# motordriver-v4_0_stspin.net
KiCad netlist of a schematic drawn in Altium Designer
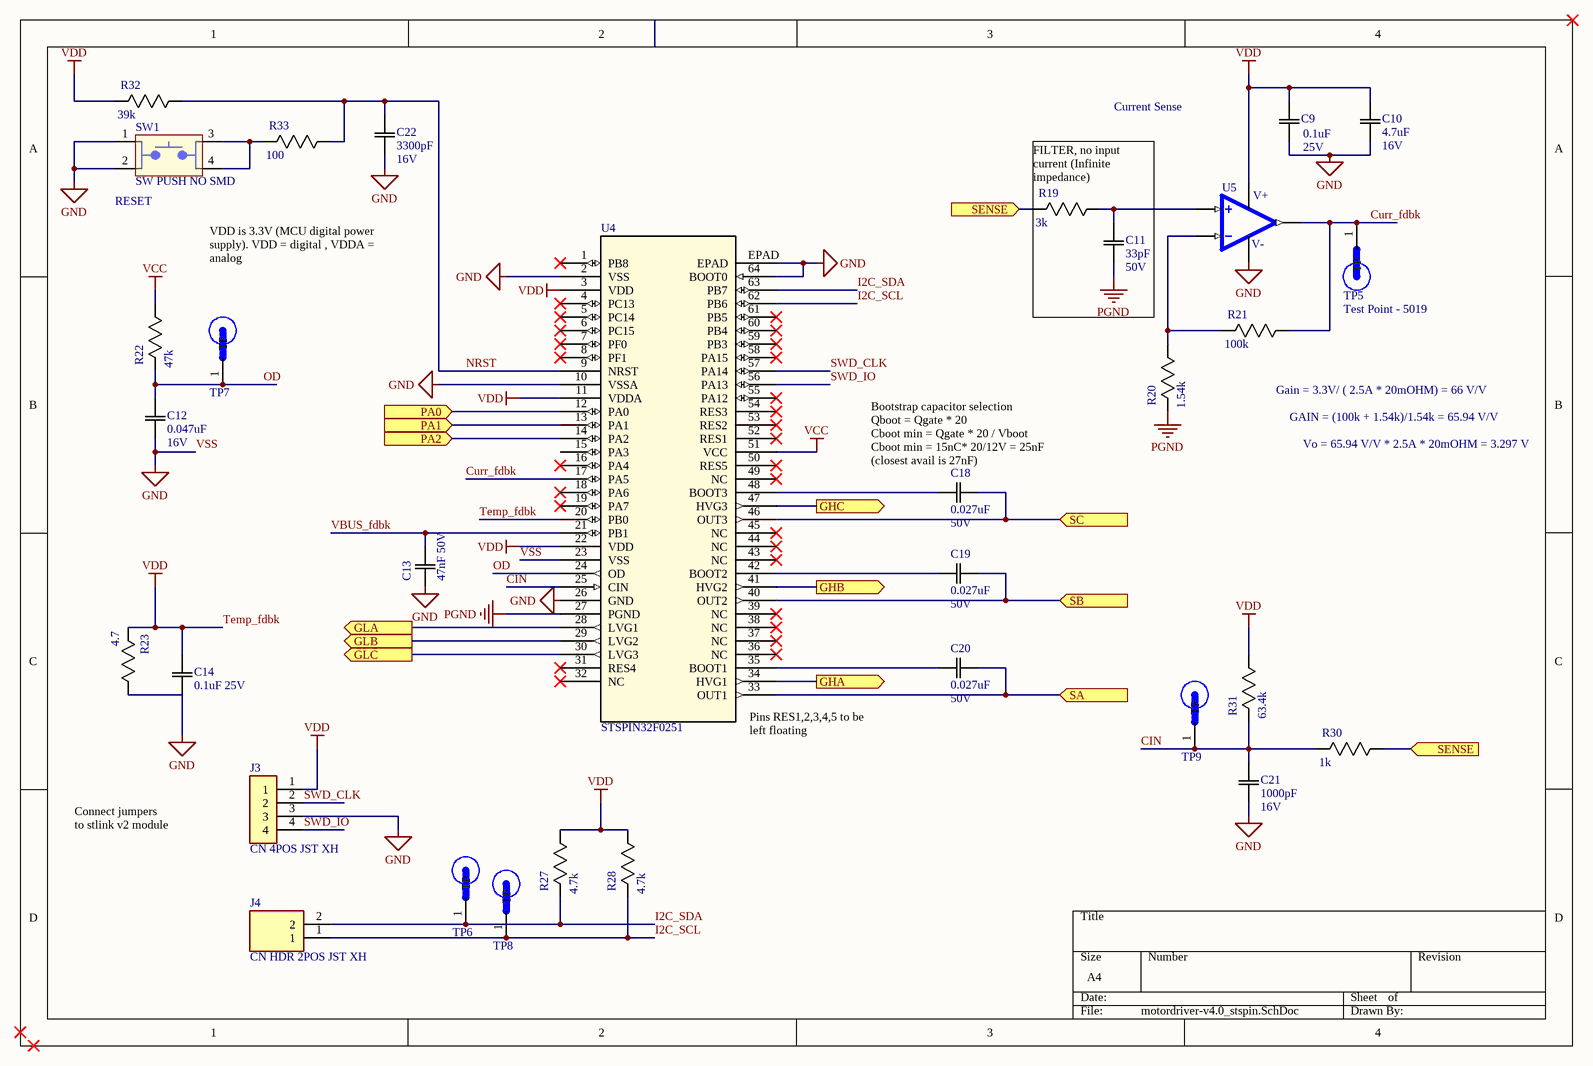
[diagram p0: motordriver-v4.0_stspin.SchDoc]

(export (version "E")
  (design (tool "Eeschema 10.0.6"))
  (components
    (comp (ref "C9")
      (value "0.1uF")
      (footprint "0805")
      (description "CAP CER 0.1UF 25V X7R 0805")
      (fields
        (field (name "TOLERANCE") "10%")
        (field (name "RATING") "25V")
        (field (name "Comment") "0.1uF 25V")
      )
      (libsource (lib "AltiumLibraries") (part "CAP 0.1uF 25V"))
    )
    (comp (ref "C10")
      (value "4.7uF")
      (footprint "0603")
      (description "CAP CER 4.7UF 16V X5R 0603/0805")
      (fields (field (name "TOLERANCE") "10%") (field (name "RATING") "16V"))
      (libsource (lib "AltiumLibraries") (part "CAP 4.7uF 16V"))
    )
    (comp (ref "C11")
      (value "33pF")
      (footprint "0603")
      (description "CAP CER 33PF 50V X7R 0603/0805")
      (fields (field (name "TOLERANCE") "10%") (field (name "RATING") "50V"))
      (libsource (lib "AltiumLibraries") (part "CAP 33pF 50V"))
    )
    (comp (ref "C12")
      (value "0.047uF")
      (footprint "0603")
      (description "CAP CER 0.047UF 16V X5R 0603/0805")
      (fields (field (name "TOLERANCE") "10%") (field (name "RATING") "16V"))
      (libsource (lib "AltiumLibraries") (part "CAP 0.047uF 16V"))
    )
    (comp (ref "C13")
      (value "47nF 50V")
      (footprint "0805")
      (description "CAP CER 0.047UF 50V X7R 0805")
      (fields (field (name "TOLERANCE") "5%"))
      (libsource (lib "AltiumLibraries") (part "CAP 47nF 50V"))
    )
    (comp (ref "C14")
      (value "0.1uF 25V")
      (footprint "0805")
      (description "CAP CER 0.1UF 25V X7R 0805")
      (fields (field (name "TOLERANCE") "10%"))
      (libsource (lib "AltiumLibraries") (part "CAP 0.1uF 25V"))
    )
    (comp (ref "C18")
      (value "0.027uF")
      (footprint "0805")
      (description "CAP CER 0.027UF 50V X7R 0805")
      (fields (field (name "TOLERANCE") "5%") (field (name "RATING") "50V"))
      (libsource (lib "AltiumLibraries") (part "CAP 0.027UF 50V X7R 0805"))
    )
    (comp (ref "C19")
      (value "0.027uF")
      (footprint "0805")
      (description "CAP CER 0.027UF 50V X7R 0805")
      (fields (field (name "TOLERANCE") "5%") (field (name "RATING") "50V"))
      (libsource (lib "AltiumLibraries") (part "CAP 0.027UF 50V X7R 0805"))
    )
    (comp (ref "C20")
      (value "0.027uF")
      (footprint "0805")
      (description "CAP CER 0.027UF 50V X7R 0805")
      (fields (field (name "TOLERANCE") "5%") (field (name "RATING") "50V"))
      (libsource (lib "AltiumLibraries") (part "CAP 0.027UF 50V X7R 0805"))
    )
    (comp (ref "C21")
      (value "1000pF")
      (footprint "0603")
      (description "CAP CER 1000PF 16V X5R 0603/0805")
      (fields (field (name "TOLERANCE") "10%") (field (name "RATING") "16V"))
      (libsource (lib "AltiumLibraries") (part "CAP 1000pF 16V"))
    )
    (comp (ref "C22")
      (value "3300pF")
      (footprint "0603")
      (description "CAP CER 3300PF 16V X5R 0603/0805")
      (fields (field (name "TOLERANCE") "10%") (field (name "RATING") "16V"))
      (libsource (lib "AltiumLibraries") (part "CAP 3300pF 16V"))
    )
    (comp (ref "J3")
      (value "CN 4POS JST XH")
      (footprint "JST_B4B-XH-A(LF)(SN)")
      (description "Connector Header Through Hole 4 position 0.098 _2.50mm_\r\nB4B-XH-A(LF)(SN)")
      (fields (field (name "MP") "B4B-XH-A_LF__SN_") (field (name "MF") "JST Sales"))
      (libsource (lib "AltiumLibraries") (part "CN 4POS JST XH"))
    )
    (comp (ref "J4")
      (value "CN HDR 2POS JST XH")
      (footprint "JST_B2B-XH-A(LF)(SN)")
      (description "Connector Header Through Hole 2 position 0.098 _2.50mm_\r\nJST XH")
      (fields (field (name "MP") "B2B-XH-A_LF__SN_") (field (name "MF") "JST Sales"))
      (libsource (lib "AltiumLibraries") (part "CN HDR 2POS JST XH"))
    )
    (comp (ref "R19")
      (value "3k")
      (footprint "0603")
      (description "RES SMD 3K OHM 5% 1/8W 0805")
      (fields (field (name "TOLERANCE") "5%"))
      (libsource (lib "AltiumLibraries") (part "RES 3k 1/8W"))
    )
    (comp (ref "R20")
      (value "1.54k")
      (footprint "0603")
      (description "RES SMD 1.54K OHM 1% 1/8W 0805")
      (fields (field (name "TOLERANCE") "1%"))
      (libsource (lib "AltiumLibraries") (part "RES 1.54k 1/8W"))
    )
    (comp (ref "R21")
      (value "100k")
      (footprint "0603")
      (description "RES SMD 100K OHM 1% 1/8W 0805")
      (fields (field (name "TOLERANCE") "1%"))
      (libsource (lib "AltiumLibraries") (part "RES 100k 1/8W - 1%"))
    )
    (comp (ref "R22")
      (value "47k")
      (footprint "0603")
      (description "RES SMD 47k OHM 5% 1/8W 0805")
      (fields (field (name "TOLERANCE") "5%"))
      (libsource (lib "AltiumLibraries") (part "RES 47k 1/8W - 5%"))
    )
    (comp (ref "R23")
      (value "4.7")
      (footprint "0603")
      (description "RES SMD 4.7 OHM 5% 1/8W 0805")
      (fields (field (name "TOLERANCE") "5%"))
      (libsource (lib "AltiumLibraries") (part "RES 4.7 1/8W"))
    )
    (comp (ref "R27")
      (value "4.7k")
      (footprint "0603")
      (description "RES SMD 4.7k OHM 1% 1/8W 0805")
      (fields (field (name "TOLERANCE") "1%"))
      (libsource (lib "AltiumLibraries") (part "RES 4.7k 1/8W - 1%"))
    )
    (comp (ref "R28")
      (value "4.7k")
      (footprint "0603")
      (description "RES SMD 4.7k OHM 1% 1/8W 0805")
      (fields (field (name "TOLERANCE") "1%"))
      (libsource (lib "AltiumLibraries") (part "RES 4.7k 1/8W - 1%"))
    )
    (comp (ref "R30")
      (value "1k")
      (footprint "0603")
      (description "RES SMD 1K OHM 5% 1/8W 0805")
      (fields (field (name "TOLERANCE") "5%"))
      (libsource (lib "AltiumLibraries") (part "RES 1k 1/8W"))
    )
    (comp (ref "R31")
      (value "63.4k")
      (footprint "0603")
      (description "RES SMD 63.4K OHM 5% 1/8W 0603/0805")
      (fields (field (name "TOLERANCE") "5%"))
      (libsource (lib "AltiumLibraries") (part "RES 63.4k 1/8W"))
    )
    (comp (ref "R32")
      (value "39k")
      (footprint "0603")
      (description "RES SMD 39K OHM 5% 1/8W 0603/0805")
      (fields (field (name "TOLERANCE") "5%"))
      (libsource (lib "AltiumLibraries") (part "RES 39k 1/8W"))
    )
    (comp (ref "R33")
      (value "100")
      (footprint "0603")
      (description "RES SMD 100 OHM 5% 1/8W 0603/0805")
      (fields (field (name "TOLERANCE") "5%"))
      (libsource (lib "AltiumLibraries") (part "RES 100.0 1/8W"))
    )
    (comp (ref "SW1")
      (value "SW PUSH NO SMD")
      (footprint "TL3305")
      (description "Tactile Switch SPST-NO Top Actuated Surface Mount 12V 50mA")
      (fields (field (name "MF") "E-Switch") (field (name "MP") "TL3305BF260QG"))
      (libsource (lib "AltiumLibraries") (part "SW PUSH NO SMD"))
    )
    (comp (ref "TP5")
      (value "Test Point - 5019")
      (footprint "TP380X203")
      (description "PC Test Point, Miniature Phosphor Bronze, Silver Plating Surface Mount Mounting Type")
      (fields (field (name "MP") "5019") (field (name "MF") "Keystone Electronics"))
      (libsource (lib "AltiumLibraries") (part "Test Point - 5019"))
    )
    (comp (ref "TP6")
      (value "Test Point - 5019")
      (footprint "TP380X203")
      (description "PC Test Point, Miniature Phosphor Bronze, Silver Plating Surface Mount Mounting Type")
      (fields (field (name "MP") "5019") (field (name "MF") "Keystone Electronics"))
      (libsource (lib "AltiumLibraries") (part "Test Point - 5019"))
    )
    (comp (ref "TP7")
      (value "Test Point - 5019")
      (footprint "TP380X203")
      (description "PC Test Point, Miniature Phosphor Bronze, Silver Plating Surface Mount Mounting Type")
      (fields (field (name "MP") "5019") (field (name "MF") "Keystone Electronics"))
      (libsource (lib "AltiumLibraries") (part "Test Point - 5019"))
    )
    (comp (ref "TP8")
      (value "Test Point - 5019")
      (footprint "TP380X203")
      (description "PC Test Point, Miniature Phosphor Bronze, Silver Plating Surface Mount Mounting Type")
      (fields (field (name "MP") "5019") (field (name "MF") "Keystone Electronics"))
      (libsource (lib "AltiumLibraries") (part "Test Point - 5019"))
    )
    (comp (ref "TP9")
      (value "Test Point - 5019")
      (footprint "TP380X203")
      (description "PC Test Point, Miniature Phosphor Bronze, Silver Plating Surface Mount Mounting Type")
      (fields (field (name "MP") "5019") (field (name "MF") "Keystone Electronics"))
      (libsource (lib "AltiumLibraries") (part "Test Point - 5019"))
    )
    (comp (ref "U4")
      (value "STSPIN32F0251")
      (footprint "STSPIN32F0251TR")
      (description "250 V BLDC THREE-PHASE CONTROLLER")
      (fields (field (name "MANUFACTURER") "STMicroelectronics"))
      (libsource (lib "AltiumLibraries") (part "STSPIN32F0251"))
    )
    (comp (ref "U5")
      (value "OP AMP TSV911ILT")
      (footprint "TSV911ILT Opamp")
      (description "IC OPAMP GP 1 CIRCUIT SOT23-5")
      (fields (field (name "MANUFACTURER") "STMicroelectronics"))
      (libsource (lib "AltiumLibraries") (part "OP AMP TSV911ILT"))
    )
  )
  (nets
    (net (code "1") (name "/CIN") (class "Default")
      (node (ref "C21") (pin "1") (pinfunction "C1_1") (pintype "passive"))
      (node (ref "R30") (pin "2") (pinfunction "R2_2") (pintype "passive"))
      (node (ref "R31") (pin "2") (pinfunction "R2_2") (pintype "passive"))
      (node (ref "TP9") (pin "1") (pinfunction "TP_1") (pintype "passive"))
      (node (ref "U4") (pin "25") (pinfunction "CIN_25") (pintype "input"))
    )
    (net (code "2") (name "/Curr_fdbk") (class "Default")
      (node (ref "R21") (pin "1") (pinfunction "R1_1") (pintype "passive"))
      (node (ref "TP5") (pin "1") (pinfunction "TP_1") (pintype "passive"))
      (node (ref "U4") (pin "17") (pinfunction "PA5_17") (pintype "bidirectional"))
      (node (ref "U5") (pin "1") (pinfunction "OUT_1") (pintype "output"))
    )
    (net (code "3") (name "/GHA") (class "Default")
      (node (ref "U4") (pin "34") (pinfunction "HVG1_34") (pintype "output"))
    )
    (net (code "4") (name "/GHB") (class "Default")
      (node (ref "U4") (pin "41") (pinfunction "HVG2_41") (pintype "output"))
    )
    (net (code "5") (name "/GHC") (class "Default")
      (node (ref "U4") (pin "47") (pinfunction "HVG3_47") (pintype "output"))
    )
    (net (code "6") (name "/GLA") (class "Default")
      (node (ref "U4") (pin "28") (pinfunction "LVG1_28") (pintype "output"))
    )
    (net (code "7") (name "/GLB") (class "Default")
      (node (ref "U4") (pin "29") (pinfunction "LVG2_29") (pintype "output"))
    )
    (net (code "8") (name "/GLC") (class "Default")
      (node (ref "U4") (pin "30") (pinfunction "LVG3_30") (pintype "output"))
    )
    (net (code "9") (name "/I2C_SCL") (class "Default")
      (node (ref "J4") (pin "1") (pinfunction "1_1") (pintype "passive"))
      (node (ref "R28") (pin "2") (pinfunction "R2_2") (pintype "passive"))
      (node (ref "TP8") (pin "1") (pinfunction "TP_1") (pintype "passive"))
      (node (ref "U4") (pin "62") (pinfunction "PB6_62") (pintype "bidirectional"))
    )
    (net (code "10") (name "/I2C_SDA") (class "Default")
      (node (ref "J4") (pin "2") (pinfunction "2_2") (pintype "passive"))
      (node (ref "R27") (pin "2") (pinfunction "R2_2") (pintype "passive"))
      (node (ref "TP6") (pin "1") (pinfunction "TP_1") (pintype "passive"))
      (node (ref "U4") (pin "63") (pinfunction "PB7_63") (pintype "bidirectional"))
    )
    (net (code "11") (name "/NRST") (class "Default")
      (node (ref "C22") (pin "2") (pinfunction "C2_2") (pintype "passive"))
      (node (ref "R32") (pin "1") (pinfunction "R1_1") (pintype "passive"))
      (node (ref "R33") (pin "1") (pinfunction "R1_1") (pintype "passive"))
      (node (ref "U4") (pin "9") (pinfunction "NRST_9") (pintype "passive"))
    )
    (net (code "12") (name "/OD") (class "Default")
      (node (ref "C12") (pin "2") (pinfunction "C2_2") (pintype "passive"))
      (node (ref "R22") (pin "2") (pinfunction "R2_2") (pintype "passive"))
      (node (ref "TP7") (pin "1") (pinfunction "TP_1") (pintype "passive"))
      (node (ref "U4") (pin "24") (pinfunction "OD_24") (pintype "output"))
    )
    (net (code "13") (name "/PA0") (class "Default")
      (node (ref "U4") (pin "12") (pinfunction "PA0_12") (pintype "bidirectional"))
    )
    (net (code "14") (name "/PA1") (class "Default")
      (node (ref "U4") (pin "13") (pinfunction "PA1_13") (pintype "bidirectional"))
    )
    (net (code "15") (name "/PA2") (class "Default")
      (node (ref "U4") (pin "14") (pinfunction "PA2_14") (pintype "bidirectional"))
    )
    (net (code "16") (name "/SA") (class "Default")
      (node (ref "C20") (pin "2") (pinfunction "2_2") (pintype "passive"))
      (node (ref "U4") (pin "33") (pinfunction "OUT1_33") (pintype "output"))
    )
    (net (code "17") (name "/SB") (class "Default")
      (node (ref "C19") (pin "2") (pinfunction "2_2") (pintype "passive"))
      (node (ref "U4") (pin "40") (pinfunction "OUT2_40") (pintype "output"))
    )
    (net (code "18") (name "/SC") (class "Default")
      (node (ref "C18") (pin "2") (pinfunction "2_2") (pintype "passive"))
      (node (ref "U4") (pin "46") (pinfunction "OUT3_46") (pintype "output"))
    )
    (net (code "19") (name "/SENSE") (class "Default")
      (node (ref "R19") (pin "2") (pinfunction "R2_2") (pintype "passive"))
      (node (ref "R30") (pin "1") (pinfunction "R1_1") (pintype "passive"))
    )
    (net (code "20") (name "/SWD_CLK") (class "Default")
      (node (ref "J3") (pin "2") (pinfunction "2_2") (pintype "passive"))
      (node (ref "U4") (pin "57") (pinfunction "PA14_57") (pintype "bidirectional"))
    )
    (net (code "21") (name "/SWD_IO") (class "Default")
      (node (ref "J3") (pin "4") (pinfunction "4_4") (pintype "passive"))
      (node (ref "U4") (pin "56") (pinfunction "PA13_56") (pintype "bidirectional"))
    )
    (net (code "22") (name "/VBUS_fdbk") (class "Default")
      (node (ref "C13") (pin "2") (pinfunction "C2_2") (pintype "passive"))
      (node (ref "U4") (pin "21") (pinfunction "PB1_21") (pintype "bidirectional"))
    )
    (net (code "23") (name "GND") (class "Default")
      (node (ref "C10") (pin "1") (pinfunction "C1_1") (pintype "passive"))
      (node (ref "C12") (pin "1") (pinfunction "C1_1") (pintype "passive"))
      (node (ref "C13") (pin "1") (pinfunction "C1_1") (pintype "passive"))
      (node (ref "C14") (pin "1") (pinfunction "C1_1") (pintype "passive"))
      (node (ref "C21") (pin "2") (pinfunction "C2_2") (pintype "passive"))
      (node (ref "C22") (pin "1") (pinfunction "C1_1") (pintype "passive"))
      (node (ref "C9") (pin "1") (pinfunction "C1_1") (pintype "passive"))
      (node (ref "J3") (pin "3") (pinfunction "3_3") (pintype "passive"))
      (node (ref "R23") (pin "1") (pinfunction "R1_1") (pintype "passive"))
      (node (ref "SW1") (pin "1") (pinfunction "1_1") (pintype "passive"))
      (node (ref "SW1") (pin "2") (pinfunction "2_2") (pintype "passive"))
      (node (ref "U4") (pin "10") (pinfunction "VSSA_10") (pintype "passive"))
      (node (ref "U4") (pin "2") (pinfunction "VSS_2") (pintype "passive"))
      (node (ref "U4") (pin "23") (pinfunction "VSS_23") (pintype "passive"))
      (node (ref "U4") (pin "26") (pinfunction "GND_26") (pintype "passive"))
      (node (ref "U4") (pin "64") (pinfunction "BOOT0_64") (pintype "input"))
      (node (ref "U4") (pin "EPAD") (pinfunction "EPAD_EPAD") (pintype "passive"))
      (node (ref "U5") (pin "2") (pinfunction "V-_2") (pintype "power_in"))
    )
    (net (code "24") (name "Net-(C11-C2)") (class "Default")
      (node (ref "C11") (pin "2") (pinfunction "C2_2") (pintype "passive"))
      (node (ref "R19") (pin "1") (pinfunction "R1_1") (pintype "passive"))
      (node (ref "U5") (pin "3") (pinfunction "IN+_3") (pintype "input"))
    )
    (net (code "25") (name "Net-(R20-R1)") (class "Default")
      (node (ref "R20") (pin "1") (pinfunction "R1_1") (pintype "passive"))
      (node (ref "R21") (pin "2") (pinfunction "R2_2") (pintype "passive"))
      (node (ref "U5") (pin "4") (pinfunction "IN-_4") (pintype "input"))
    )
    (net (code "26") (name "Net-(R33-R2)") (class "Default")
      (node (ref "R33") (pin "2") (pinfunction "R2_2") (pintype "passive"))
      (node (ref "SW1") (pin "3") (pinfunction "3_3") (pintype "passive"))
      (node (ref "SW1") (pin "4") (pinfunction "4_4") (pintype "passive"))
    )
    (net (code "27") (name "Net-(U4-BOOT1)") (class "Default")
      (node (ref "C20") (pin "1") (pinfunction "1_1") (pintype "passive"))
      (node (ref "U4") (pin "35") (pinfunction "BOOT1_35") (pintype "power_in"))
    )
    (net (code "28") (name "Net-(U4-BOOT2)") (class "Default")
      (node (ref "C19") (pin "1") (pinfunction "1_1") (pintype "passive"))
      (node (ref "U4") (pin "42") (pinfunction "BOOT2_42") (pintype "power_in"))
    )
    (net (code "29") (name "Net-(U4-BOOT3)") (class "Default")
      (node (ref "C18") (pin "1") (pinfunction "1_1") (pintype "passive"))
      (node (ref "U4") (pin "48") (pinfunction "BOOT3_48") (pintype "power_in"))
    )
    (net (code "30") (name "PGND") (class "Default")
      (node (ref "C11") (pin "1") (pinfunction "C1_1") (pintype "passive"))
      (node (ref "R20") (pin "2") (pinfunction "R2_2") (pintype "passive"))
      (node (ref "U4") (pin "27") (pinfunction "PGND_27") (pintype "passive"))
    )
    (net (code "31") (name "VCC") (class "Default")
      (node (ref "R22") (pin "1") (pinfunction "R1_1") (pintype "passive"))
      (node (ref "U4") (pin "51") (pinfunction "VCC_51") (pintype "power_in"))
    )
    (net (code "32") (name "VDD") (class "Default")
      (node (ref "C10") (pin "2") (pinfunction "C2_2") (pintype "passive"))
      (node (ref "C14") (pin "2") (pinfunction "C2_2") (pintype "passive"))
      (node (ref "C9") (pin "2") (pinfunction "C2_2") (pintype "passive"))
      (node (ref "J3") (pin "1") (pinfunction "1_1") (pintype "passive"))
      (node (ref "R23") (pin "2") (pinfunction "R2_2") (pintype "passive"))
      (node (ref "R27") (pin "1") (pinfunction "R1_1") (pintype "passive"))
      (node (ref "R28") (pin "1") (pinfunction "R1_1") (pintype "passive"))
      (node (ref "R31") (pin "1") (pinfunction "R1_1") (pintype "passive"))
      (node (ref "R32") (pin "2") (pinfunction "R2_2") (pintype "passive"))
      (node (ref "U4") (pin "11") (pinfunction "VDDA_11") (pintype "power_in"))
      (node (ref "U4") (pin "20") (pinfunction "PB0_20") (pintype "bidirectional"))
      (node (ref "U4") (pin "22") (pinfunction "VDD_22") (pintype "power_in"))
      (node (ref "U4") (pin "3") (pinfunction "VDD_3") (pintype "power_in"))
      (node (ref "U5") (pin "5") (pinfunction "V+_5") (pintype "power_in"))
    )
    (net (code "33") (name "unconnected-(U4-NC-Pad32)") (class "Default")
      (node (ref "U4") (pin "32") (pinfunction "NC_32") (pintype "passive+no_connect"))
    )
    (net (code "34") (name "unconnected-(U4-NC-Pad36)") (class "Default")
      (node (ref "U4") (pin "36") (pinfunction "NC_36") (pintype "passive+no_connect"))
    )
    (net (code "35") (name "unconnected-(U4-NC-Pad37)") (class "Default")
      (node (ref "U4") (pin "37") (pinfunction "NC_37") (pintype "passive+no_connect"))
    )
    (net (code "36") (name "unconnected-(U4-NC-Pad38)") (class "Default")
      (node (ref "U4") (pin "38") (pinfunction "NC_38") (pintype "passive+no_connect"))
    )
    (net (code "37") (name "unconnected-(U4-NC-Pad39)") (class "Default")
      (node (ref "U4") (pin "39") (pinfunction "NC_39") (pintype "passive+no_connect"))
    )
    (net (code "38") (name "unconnected-(U4-NC-Pad43)") (class "Default")
      (node (ref "U4") (pin "43") (pinfunction "NC_43") (pintype "passive+no_connect"))
    )
    (net (code "39") (name "unconnected-(U4-NC-Pad44)") (class "Default")
      (node (ref "U4") (pin "44") (pinfunction "NC_44") (pintype "passive+no_connect"))
    )
    (net (code "40") (name "unconnected-(U4-NC-Pad45)") (class "Default")
      (node (ref "U4") (pin "45") (pinfunction "NC_45") (pintype "passive+no_connect"))
    )
    (net (code "41") (name "unconnected-(U4-NC-Pad49)") (class "Default")
      (node (ref "U4") (pin "49") (pinfunction "NC_49") (pintype "passive+no_connect"))
    )
    (net (code "42") (name "unconnected-(U4-PA3-Pad15)") (class "Default")
      (node (ref "U4") (pin "15") (pinfunction "PA3_15") (pintype "bidirectional"))
    )
    (net (code "43") (name "unconnected-(U4-PA4-Pad16)") (class "Default")
      (node (ref "U4") (pin "16") (pinfunction "PA4_16") (pintype "bidirectional+no_connect"))
    )
    (net (code "44") (name "unconnected-(U4-PA6-Pad18)") (class "Default")
      (node (ref "U4") (pin "18") (pinfunction "PA6_18") (pintype "bidirectional+no_connect"))
    )
    (net (code "45") (name "unconnected-(U4-PA7-Pad19)") (class "Default")
      (node (ref "U4") (pin "19") (pinfunction "PA7_19") (pintype "bidirectional+no_connect"))
    )
    (net (code "46") (name "unconnected-(U4-PA12-Pad55)") (class "Default")
      (node (ref "U4") (pin "55") (pinfunction "PA12_55") (pintype "bidirectional+no_connect"))
    )
    (net (code "47") (name "unconnected-(U4-PA15-Pad58)") (class "Default")
      (node (ref "U4") (pin "58") (pinfunction "PA15_58") (pintype "bidirectional+no_connect"))
    )
    (net (code "48") (name "unconnected-(U4-PB3-Pad59)") (class "Default")
      (node (ref "U4") (pin "59") (pinfunction "PB3_59") (pintype "bidirectional+no_connect"))
    )
    (net (code "49") (name "unconnected-(U4-PB4-Pad60)") (class "Default")
      (node (ref "U4") (pin "60") (pinfunction "PB4_60") (pintype "bidirectional+no_connect"))
    )
    (net (code "50") (name "unconnected-(U4-PB5-Pad61)") (class "Default")
      (node (ref "U4") (pin "61") (pinfunction "PB5_61") (pintype "bidirectional+no_connect"))
    )
    (net (code "51") (name "unconnected-(U4-PB8-Pad1)") (class "Default")
      (node (ref "U4") (pin "1") (pinfunction "PB8_1") (pintype "bidirectional+no_connect"))
    )
    (net (code "52") (name "unconnected-(U4-PC13-Pad4)") (class "Default")
      (node (ref "U4") (pin "4") (pinfunction "PC13_4") (pintype "bidirectional+no_connect"))
    )
    (net (code "53") (name "unconnected-(U4-PC14-Pad5)") (class "Default")
      (node (ref "U4") (pin "5") (pinfunction "PC14_5") (pintype "bidirectional+no_connect"))
    )
    (net (code "54") (name "unconnected-(U4-PC15-Pad6)") (class "Default")
      (node (ref "U4") (pin "6") (pinfunction "PC15_6") (pintype "bidirectional+no_connect"))
    )
    (net (code "55") (name "unconnected-(U4-PF0-Pad7)") (class "Default")
      (node (ref "U4") (pin "7") (pinfunction "PF0_7") (pintype "bidirectional+no_connect"))
    )
    (net (code "56") (name "unconnected-(U4-PF1-Pad8)") (class "Default")
      (node (ref "U4") (pin "8") (pinfunction "PF1_8") (pintype "bidirectional+no_connect"))
    )
    (net (code "57") (name "unconnected-(U4-RES1-Pad52)") (class "Default")
      (node (ref "U4") (pin "52") (pinfunction "RES1_52") (pintype "passive+no_connect"))
    )
    (net (code "58") (name "unconnected-(U4-RES2-Pad53)") (class "Default")
      (node (ref "U4") (pin "53") (pinfunction "RES2_53") (pintype "passive+no_connect"))
    )
    (net (code "59") (name "unconnected-(U4-RES3-Pad54)") (class "Default")
      (node (ref "U4") (pin "54") (pinfunction "RES3_54") (pintype "passive+no_connect"))
    )
    (net (code "60") (name "unconnected-(U4-RES4-Pad31)") (class "Default")
      (node (ref "U4") (pin "31") (pinfunction "RES4_31") (pintype "passive+no_connect"))
    )
    (net (code "61") (name "unconnected-(U4-RES5-Pad50)") (class "Default")
      (node (ref "U4") (pin "50") (pinfunction "RES5_50") (pintype "passive+no_connect"))
    )
  )
)
